# Page_G_ZLG_3G.net
KiCad netlist of a schematic drawn in Altium Designer
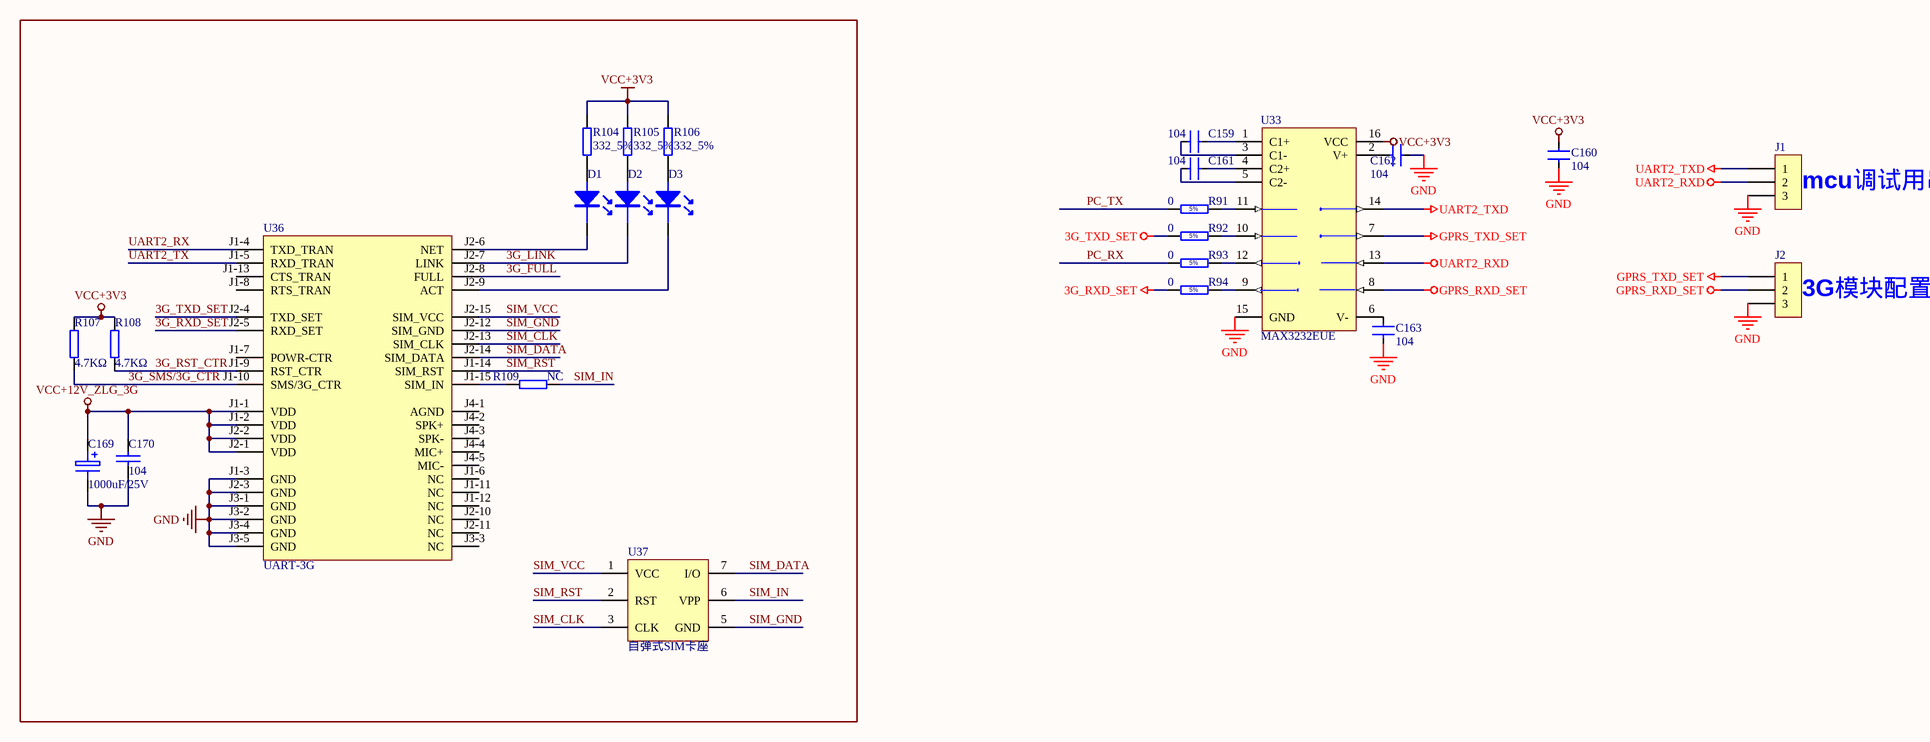
[diagram p0: Page G_ZLG_3G.SchDoc]

(export (version "E")
  (design (tool "Eeschema 10.0.6"))
  (components
    (comp (ref "C159")
      (value "104")
      (footprint "0603C")
      (description "C-X5R/X7R")
      (libsource (lib "贴片电阻电容") (part "C-X5R/X7R"))
    )
    (comp (ref "C160")
      (value "104")
      (footprint "0603C")
      (description "C-X5R/X7R")
      (libsource (lib "贴片电阻电容") (part "C-X5R/X7R"))
    )
    (comp (ref "C161")
      (value "104")
      (footprint "0603C")
      (description "C-X5R/X7R")
      (libsource (lib "贴片电阻电容") (part "C-X5R/X7R"))
    )
    (comp (ref "C162")
      (value "104")
      (footprint "0603C")
      (description "C-X5R/X7R")
      (libsource (lib "贴片电阻电容") (part "C-X5R/X7R"))
    )
    (comp (ref "C163")
      (value "104")
      (footprint "0603C")
      (description "C-X5R/X7R")
      (libsource (lib "贴片电阻电容") (part "C-X5R/X7R"))
    )
    (comp (ref "C169")
      (value "1000uF/25V")
      (footprint "C_10_10MM")
      (description "CD11")
      (libsource (lib "电解电容") (part "1000uF/25V"))
    )
    (comp (ref "C170")
      (value "104")
      (footprint "0805C")
      (description "CC")
      (libsource (lib "无极性电容") (part "0.1uF"))
    )
    (comp (ref "D1")
      (value "LED")
      (footprint "LED_3MM")
      (libsource (lib "Miscellaneous Devices") (part "LED"))
    )
    (comp (ref "D2")
      (value "LED")
      (footprint "LED_3MM")
      (libsource (lib "Miscellaneous Devices") (part "LED"))
    )
    (comp (ref "D3")
      (value "LED")
      (footprint "LED_3MM")
      (libsource (lib "Miscellaneous Devices") (part "LED"))
    )
    (comp (ref "J1")
      (value "~")
      (footprint "CHAZUO3*2.54")
      (description "CN-SIP3-2.54")
      (libsource (lib "接插件") (part "SIP3-2.54"))
    )
    (comp (ref "J2")
      (value "~")
      (footprint "CHAZUO3*2.54")
      (description "CN-SIP3-2.54")
      (libsource (lib "接插件") (part "SIP3-2.54"))
    )
    (comp (ref "R91")
      (value "0")
      (footprint "0603R")
      (description "Resistor - 5%")
      (libsource (lib "贴片电阻电容") (part "Resistor - 5%"))
    )
    (comp (ref "R92")
      (value "0")
      (footprint "0603R")
      (description "Resistor - 5%")
      (libsource (lib "贴片电阻电容") (part "Resistor - 5%"))
    )
    (comp (ref "R93")
      (value "0")
      (footprint "0603R")
      (description "Resistor - 5%")
      (libsource (lib "贴片电阻电容") (part "Resistor - 5%"))
    )
    (comp (ref "R94")
      (value "0")
      (footprint "0603R")
      (description "Resistor - 5%")
      (libsource (lib "贴片电阻电容") (part "Resistor - 5%"))
    )
    (comp (ref "R104") (value "332_5%") (footprint "0603R") (libsource (lib "贴片电阻") (part "R-0805R")))
    (comp (ref "R105") (value "332_5%") (footprint "0603R") (libsource (lib "贴片电阻") (part "R-0805R")))
    (comp (ref "R106") (value "332_5%") (footprint "0603R") (libsource (lib "贴片电阻") (part "R-0805R")))
    (comp (ref "R107") (value "4.7KΩ") (footprint "0603R") (libsource (lib "贴片电阻") (part "1K-0805R")))
    (comp (ref "R108") (value "4.7KΩ") (footprint "0603R") (libsource (lib "贴片电阻") (part "1K-0805R")))
    (comp (ref "R109") (value "NC") (footprint "0603R") (libsource (lib "贴片电阻") (part "1K-0805R")))
    (comp (ref "U33")
      (value "MAX3232EUE")
      (footprint "TSSOP16")
      (description "3.0V TO 5.5V, Low-Power, up to 1Mbps, True RS-232 Transceiver Using Four 0.1礔 External Capacitor")
      (fields (field (name "PUBLISHER") "Altium Limited"))
      (libsource (lib "Maxim Communication Transceiver") (part "MAX3232EUE"))
    )
    (comp (ref "U36")
      (value "UART-3G")
      (footprint "ZWD_35DP_UART-3G")
      (libsource (lib "其他元器件") (part "ZWD-35DP-UART-3G"))
    )
    (comp (ref "U37") (value "自弹式SIM卡座") (footprint "SIM_PUSH") (libsource (lib "其他元器件") (part "SIM_PUSH")))
  )
  (nets
    (net (code "1") (name "/3G_FULL") (class "Default")
      (node (ref "U36") (pin "J2-8") (pinfunction "FULL_J2-8") (pintype "passive"))
    )
    (net (code "2") (name "/3G_LINK") (class "Default")
      (node (ref "D2") (pin "K") (pinfunction "2_K") (pintype "passive"))
      (node (ref "U36") (pin "J2-7") (pinfunction "LINK_J2-7") (pintype "passive"))
    )
    (net (code "3") (name "/3G_RST_CTR") (class "Default")
      (node (ref "R108") (pin "2") (pinfunction "2_2") (pintype "passive"))
      (node (ref "U36") (pin "J1-9") (pinfunction "RST_CTR_J1-9") (pintype "passive"))
    )
    (net (code "4") (name "/3G_SMS{slash}3G_CTR") (class "Default")
      (node (ref "R107") (pin "2") (pinfunction "2_2") (pintype "passive"))
      (node (ref "U36") (pin "J1-10") (pinfunction "SMS/3G_CTR_J1-10") (pintype "passive"))
    )
    (net (code "5") (name "/PC_RX") (class "Default")
      (node (ref "R93") (pin "1") (pinfunction "1_1") (pintype "passive"))
    )
    (net (code "6") (name "/PC_TX") (class "Default")
      (node (ref "R91") (pin "1") (pinfunction "1_1") (pintype "passive"))
    )
    (net (code "7") (name "/SIM_CLK") (class "Default")
      (node (ref "U36") (pin "J2-13") (pinfunction "SIM_CLK_J2-13") (pintype "passive"))
      (node (ref "U37") (pin "3") (pinfunction "CLK_3") (pintype "passive"))
    )
    (net (code "8") (name "/SIM_DATA") (class "Default")
      (node (ref "U36") (pin "J2-14") (pinfunction "SIM_DATA_J2-14") (pintype "passive"))
      (node (ref "U37") (pin "7") (pinfunction "I/O_7") (pintype "passive"))
    )
    (net (code "9") (name "/SIM_GND") (class "Default")
      (node (ref "U36") (pin "J2-12") (pinfunction "SIM_GND_J2-12") (pintype "passive"))
      (node (ref "U37") (pin "5") (pinfunction "GND_5") (pintype "passive"))
    )
    (net (code "10") (name "/SIM_IN") (class "Default")
      (node (ref "R109") (pin "2") (pinfunction "2_2") (pintype "passive"))
      (node (ref "U37") (pin "6") (pinfunction "VPP_6") (pintype "passive"))
    )
    (net (code "11") (name "/SIM_RST") (class "Default")
      (node (ref "U36") (pin "J1-14") (pinfunction "SIM_RST_J1-14") (pintype "passive"))
      (node (ref "U37") (pin "2") (pinfunction "RST_2") (pintype "passive"))
    )
    (net (code "12") (name "/SIM_VCC") (class "Default")
      (node (ref "U36") (pin "J2-15") (pinfunction "SIM_VCC_J2-15") (pintype "passive"))
      (node (ref "U37") (pin "1") (pinfunction "VCC_1") (pintype "passive"))
    )
    (net (code "13") (name "/UART2_RX") (class "Default")
      (node (ref "U36") (pin "J1-4") (pinfunction "TXD_TRAN_J1-4") (pintype "passive"))
    )
    (net (code "14") (name "/UART2_TX") (class "Default")
      (node (ref "U36") (pin "J1-5") (pinfunction "RXD_TRAN_J1-5") (pintype "passive"))
    )
    (net (code "15") (name "3G_RXD_SET") (class "Default")
      (node (ref "R94") (pin "1") (pinfunction "1_1") (pintype "passive"))
      (node (ref "U36") (pin "J2-5") (pinfunction "RXD_SET_J2-5") (pintype "passive"))
    )
    (net (code "16") (name "3G_TXD_SET") (class "Default")
      (node (ref "R92") (pin "1") (pinfunction "1_1") (pintype "passive"))
      (node (ref "U36") (pin "J2-4") (pinfunction "TXD_SET_J2-4") (pintype "passive"))
    )
    (net (code "17") (name "GND") (class "Default")
      (node (ref "C160") (pin "1") (pinfunction "1_1") (pintype "passive"))
      (node (ref "C162") (pin "2") (pinfunction "2_2") (pintype "passive"))
      (node (ref "C163") (pin "2") (pinfunction "2_2") (pintype "passive"))
      (node (ref "C169") (pin "2") (pinfunction "2_2") (pintype "passive"))
      (node (ref "C170") (pin "2") (pintype "passive"))
      (node (ref "J1") (pin "3") (pinfunction "3_3") (pintype "passive"))
      (node (ref "J2") (pin "3") (pinfunction "3_3") (pintype "passive"))
      (node (ref "U33") (pin "15") (pinfunction "GND_15") (pintype "power_in"))
      (node (ref "U36") (pin "J1-3") (pinfunction "GND_J1-3") (pintype "passive"))
      (node (ref "U36") (pin "J2-3") (pinfunction "GND_J2-3") (pintype "passive"))
      (node (ref "U36") (pin "J3-1") (pinfunction "GND_J3-1") (pintype "passive"))
      (node (ref "U36") (pin "J3-2") (pinfunction "GND_J3-2") (pintype "passive"))
      (node (ref "U36") (pin "J3-4") (pinfunction "GND_J3-4") (pintype "passive"))
      (node (ref "U36") (pin "J3-5") (pinfunction "GND_J3-5") (pintype "passive"))
    )
    (net (code "18") (name "GPRS_RXD_SET") (class "Default")
      (node (ref "J2") (pin "2") (pinfunction "2_2") (pintype "passive"))
      (node (ref "U33") (pin "8") (pinfunction "R2IN_8") (pintype "input"))
    )
    (net (code "19") (name "GPRS_TXD_SET") (class "Default")
      (node (ref "J2") (pin "1") (pinfunction "1_1") (pintype "passive"))
      (node (ref "U33") (pin "7") (pinfunction "T2OUT_7") (pintype "output"))
    )
    (net (code "20") (name "Net-(D1-1)") (class "Default")
      (node (ref "D1") (pin "A") (pinfunction "1_A") (pintype "passive"))
      (node (ref "R104") (pin "2") (pinfunction "2_2") (pintype "passive"))
    )
    (net (code "21") (name "Net-(D1-2)") (class "Default")
      (node (ref "D1") (pin "K") (pinfunction "2_K") (pintype "passive"))
      (node (ref "U36") (pin "J2-6") (pinfunction "NET_J2-6") (pintype "passive"))
    )
    (net (code "22") (name "Net-(D2-1)") (class "Default")
      (node (ref "D2") (pin "A") (pinfunction "1_A") (pintype "passive"))
      (node (ref "R105") (pin "2") (pinfunction "2_2") (pintype "passive"))
    )
    (net (code "23") (name "Net-(D3-1)") (class "Default")
      (node (ref "D3") (pin "A") (pinfunction "1_A") (pintype "passive"))
      (node (ref "R106") (pin "2") (pinfunction "2_2") (pintype "passive"))
    )
    (net (code "24") (name "Net-(D3-2)") (class "Default")
      (node (ref "D3") (pin "K") (pinfunction "2_K") (pintype "passive"))
      (node (ref "U36") (pin "J2-9") (pinfunction "ACT_J2-9") (pintype "passive"))
    )
    (net (code "25") (name "Net-(U33-C1+)") (class "Default")
      (node (ref "C159") (pin "1") (pinfunction "1_1") (pintype "passive"))
      (node (ref "U33") (pin "1") (pinfunction "C1+_1") (pintype "passive"))
    )
    (net (code "26") (name "Net-(U33-C1-)") (class "Default")
      (node (ref "C159") (pin "2") (pinfunction "2_2") (pintype "passive"))
      (node (ref "U33") (pin "3") (pinfunction "C1-_3") (pintype "passive"))
    )
    (net (code "27") (name "Net-(U33-C2+)") (class "Default")
      (node (ref "C161") (pin "1") (pinfunction "1_1") (pintype "passive"))
      (node (ref "U33") (pin "4") (pinfunction "C2+_4") (pintype "passive"))
    )
    (net (code "28") (name "Net-(U33-C2-)") (class "Default")
      (node (ref "C161") (pin "2") (pinfunction "2_2") (pintype "passive"))
      (node (ref "U33") (pin "5") (pinfunction "C2-_5") (pintype "passive"))
    )
    (net (code "29") (name "Net-(U33-R1OUT)") (class "Default")
      (node (ref "R93") (pin "2") (pinfunction "2_2") (pintype "passive"))
      (node (ref "U33") (pin "12") (pinfunction "R1OUT_12") (pintype "output"))
    )
    (net (code "30") (name "Net-(U33-R2OUT)") (class "Default")
      (node (ref "R94") (pin "2") (pinfunction "2_2") (pintype "passive"))
      (node (ref "U33") (pin "9") (pinfunction "R2OUT_9") (pintype "output"))
    )
    (net (code "31") (name "Net-(U33-T1IN)") (class "Default")
      (node (ref "R91") (pin "2") (pinfunction "2_2") (pintype "passive"))
      (node (ref "U33") (pin "11") (pinfunction "T1IN_11") (pintype "input"))
    )
    (net (code "32") (name "Net-(U33-T2IN)") (class "Default")
      (node (ref "R92") (pin "2") (pinfunction "2_2") (pintype "passive"))
      (node (ref "U33") (pin "10") (pinfunction "T2IN_10") (pintype "input"))
    )
    (net (code "33") (name "Net-(U33-V+)") (class "Default")
      (node (ref "C162") (pin "1") (pinfunction "1_1") (pintype "passive"))
      (node (ref "U33") (pin "2") (pinfunction "V+_2") (pintype "power_in"))
    )
    (net (code "34") (name "Net-(U33-V-)") (class "Default")
      (node (ref "C163") (pin "1") (pinfunction "1_1") (pintype "passive"))
      (node (ref "U33") (pin "6") (pinfunction "V-_6") (pintype "power_in"))
    )
    (net (code "35") (name "Net-(U36-SIM_IN)") (class "Default")
      (node (ref "R109") (pin "1") (pinfunction "1_1") (pintype "passive"))
      (node (ref "U36") (pin "J1-15") (pinfunction "SIM_IN_J1-15") (pintype "passive"))
    )
    (net (code "36") (name "UART2_RXD") (class "Default")
      (node (ref "J1") (pin "2") (pinfunction "2_2") (pintype "passive"))
      (node (ref "U33") (pin "13") (pinfunction "R1IN_13") (pintype "input"))
    )
    (net (code "37") (name "UART2_TXD") (class "Default")
      (node (ref "J1") (pin "1") (pinfunction "1_1") (pintype "passive"))
      (node (ref "U33") (pin "14") (pinfunction "T1OUT_14") (pintype "output"))
    )
    (net (code "38") (name "VCC+3V3") (class "Default")
      (node (ref "C160") (pin "2") (pinfunction "2_2") (pintype "passive"))
      (node (ref "R104") (pin "1") (pinfunction "1_1") (pintype "passive"))
      (node (ref "R105") (pin "1") (pinfunction "1_1") (pintype "passive"))
      (node (ref "R106") (pin "1") (pinfunction "1_1") (pintype "passive"))
      (node (ref "R107") (pin "1") (pinfunction "1_1") (pintype "passive"))
      (node (ref "R108") (pin "1") (pinfunction "1_1") (pintype "passive"))
      (node (ref "U33") (pin "16") (pinfunction "VCC_16") (pintype "power_in"))
    )
    (net (code "39") (name "VCC+12V_ZLG_3G") (class "Default")
      (node (ref "C169") (pin "1") (pinfunction "1_1") (pintype "passive"))
      (node (ref "C170") (pin "1") (pintype "passive"))
      (node (ref "U36") (pin "J1-1") (pinfunction "VDD_J1-1") (pintype "passive"))
      (node (ref "U36") (pin "J1-2") (pinfunction "VDD_J1-2") (pintype "passive"))
      (node (ref "U36") (pin "J2-1") (pinfunction "VDD_J2-1") (pintype "passive"))
      (node (ref "U36") (pin "J2-2") (pinfunction "VDD_J2-2") (pintype "passive"))
    )
    (net (code "40") (name "unconnected-(U36-AGND-PadJ4-1)") (class "Default")
      (node (ref "U36") (pin "J4-1") (pinfunction "AGND_J4-1") (pintype "passive"))
    )
    (net (code "41") (name "unconnected-(U36-CTS_TRAN-PadJ1-13)") (class "Default")
      (node (ref "U36") (pin "J1-13") (pinfunction "CTS_TRAN_J1-13") (pintype "passive"))
    )
    (net (code "42") (name "unconnected-(U36-MIC+-PadJ4-4)") (class "Default")
      (node (ref "U36") (pin "J4-4") (pinfunction "MIC+_J4-4") (pintype "passive"))
    )
    (net (code "43") (name "unconnected-(U36-MIC--PadJ4-5)") (class "Default")
      (node (ref "U36") (pin "J4-5") (pinfunction "MIC-_J4-5") (pintype "passive"))
    )
    (net (code "44") (name "unconnected-(U36-NC-PadJ1-6)") (class "Default")
      (node (ref "U36") (pin "J1-6") (pinfunction "NC_J1-6") (pintype "passive"))
    )
    (net (code "45") (name "unconnected-(U36-NC-PadJ1-11)") (class "Default")
      (node (ref "U36") (pin "J1-11") (pinfunction "NC_J1-11") (pintype "passive"))
    )
    (net (code "46") (name "unconnected-(U36-NC-PadJ1-12)") (class "Default")
      (node (ref "U36") (pin "J1-12") (pinfunction "NC_J1-12") (pintype "passive"))
    )
    (net (code "47") (name "unconnected-(U36-NC-PadJ2-10)") (class "Default")
      (node (ref "U36") (pin "J2-10") (pinfunction "NC_J2-10") (pintype "passive"))
    )
    (net (code "48") (name "unconnected-(U36-NC-PadJ2-11)") (class "Default")
      (node (ref "U36") (pin "J2-11") (pinfunction "NC_J2-11") (pintype "passive"))
    )
    (net (code "49") (name "unconnected-(U36-NC-PadJ3-3)") (class "Default")
      (node (ref "U36") (pin "J3-3") (pinfunction "NC_J3-3") (pintype "passive"))
    )
    (net (code "50") (name "unconnected-(U36-POWR-CTR-PadJ1-7)") (class "Default")
      (node (ref "U36") (pin "J1-7") (pinfunction "POWR-CTR_J1-7") (pintype "passive"))
    )
    (net (code "51") (name "unconnected-(U36-RTS_TRAN-PadJ1-8)") (class "Default")
      (node (ref "U36") (pin "J1-8") (pinfunction "RTS_TRAN_J1-8") (pintype "passive"))
    )
    (net (code "52") (name "unconnected-(U36-SPK+-PadJ4-2)") (class "Default")
      (node (ref "U36") (pin "J4-2") (pinfunction "SPK+_J4-2") (pintype "passive"))
    )
    (net (code "53") (name "unconnected-(U36-SPK--PadJ4-3)") (class "Default")
      (node (ref "U36") (pin "J4-3") (pinfunction "SPK-_J4-3") (pintype "passive"))
    )
  )
)
